# M715X.net
KiCad netlist of a schematic drawn in EAGLE
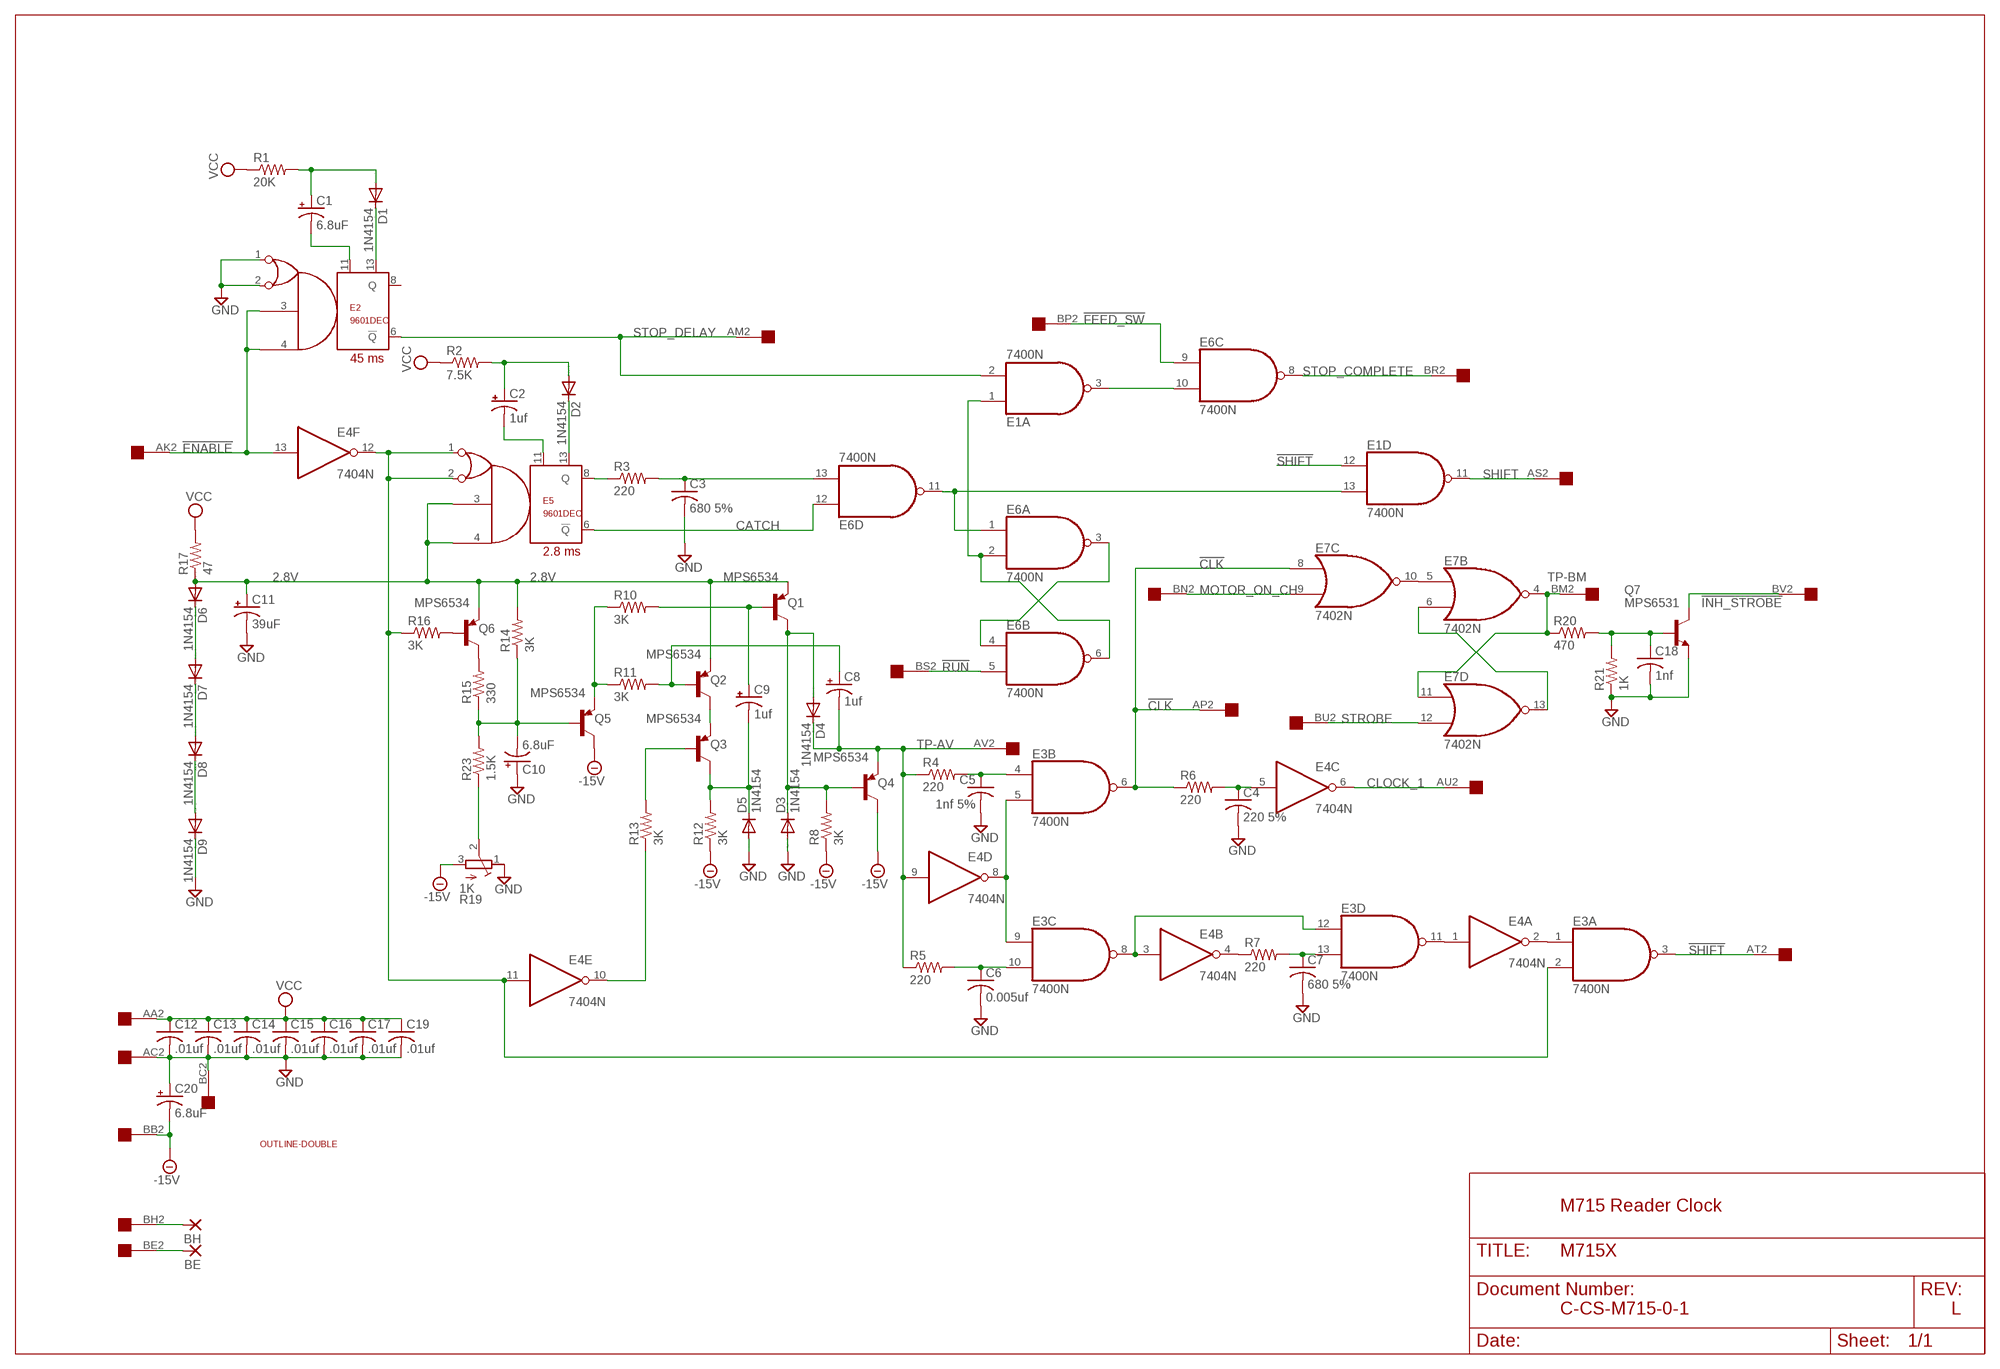
[diagram p0: schematic, sheet 1]

(export (version "E")
  (design (tool "Eeschema 10.0.6"))
  (components
    (comp (ref "BE")
      (value "1,6/0,8")
      (footprint "eagle-import:1,6_0,8")
      (libsource (lib "eagle-import") (part "1,6/0,8"))
    )
    (comp (ref "BH")
      (value "1,6/0,8")
      (footprint "eagle-import:1,6_0,8")
      (libsource (lib "eagle-import") (part "1,6/0,8"))
    )
    (comp (ref "C1")
      (value "6.8uF")
      (footprint "eagle-import:E12-8")
      (libsource (lib "eagle-import") (part "CPOL-USE20-8AXIAL"))
    )
    (comp (ref "C2")
      (value "1uf")
      (footprint "eagle-import:E15-5")
      (libsource (lib "eagle-import") (part "CPOL-USE15-5AXIAL"))
    )
    (comp (ref "C3")
      (value "680 5%")
      (footprint "eagle-import:C050-025X075")
      (libsource (lib "eagle-import") (part "C-US050-025X075"))
    )
    (comp (ref "C4")
      (value "220 5%")
      (footprint "eagle-import:C050-025X075")
      (libsource (lib "eagle-import") (part "C-US050-025X075"))
    )
    (comp (ref "C5")
      (value "1nf 5%")
      (footprint "eagle-import:C050-025X075")
      (libsource (lib "eagle-import") (part "C-US050-025X075"))
    )
    (comp (ref "C6")
      (value "0.005uf")
      (footprint "eagle-import:C050-025X075")
      (libsource (lib "eagle-import") (part "C-US050-025X075"))
    )
    (comp (ref "C7")
      (value "680 5%")
      (footprint "eagle-import:C050-025X075")
      (libsource (lib "eagle-import") (part "C-US050-025X075"))
    )
    (comp (ref "C8")
      (value "1uf")
      (footprint "eagle-import:E15-5")
      (libsource (lib "eagle-import") (part "CPOL-USE15-5AXIAL"))
    )
    (comp (ref "C9")
      (value "1uf")
      (footprint "eagle-import:E15-5")
      (libsource (lib "eagle-import") (part "CPOL-USE15-5AXIAL"))
    )
    (comp (ref "C10")
      (value "6.8uF")
      (footprint "eagle-import:E12-8")
      (libsource (lib "eagle-import") (part "CPOL-USE20-8AXIAL"))
    )
    (comp (ref "C11")
      (value "39uF")
      (footprint "eagle-import:E12-8")
      (libsource (lib "eagle-import") (part "CPOL-USE20-8AXIAL"))
    )
    (comp (ref "C12")
      (value ".01uf")
      (footprint "eagle-import:C050-025X075")
      (libsource (lib "eagle-import") (part "C-US050-025X075"))
    )
    (comp (ref "C13")
      (value ".01uf")
      (footprint "eagle-import:C050-025X075")
      (libsource (lib "eagle-import") (part "C-US050-025X075"))
    )
    (comp (ref "C14")
      (value ".01uf")
      (footprint "eagle-import:C050-025X075")
      (libsource (lib "eagle-import") (part "C-US050-025X075"))
    )
    (comp (ref "C15")
      (value ".01uf")
      (footprint "eagle-import:C050-025X075")
      (libsource (lib "eagle-import") (part "C-US050-025X075"))
    )
    (comp (ref "C16")
      (value ".01uf")
      (footprint "eagle-import:C050-025X075")
      (libsource (lib "eagle-import") (part "C-US050-025X075"))
    )
    (comp (ref "C17")
      (value ".01uf")
      (footprint "eagle-import:C050-025X075")
      (libsource (lib "eagle-import") (part "C-US050-025X075"))
    )
    (comp (ref "C18")
      (value "1nf")
      (footprint "eagle-import:C050-025X075")
      (libsource (lib "eagle-import") (part "C-US050-025X075"))
    )
    (comp (ref "C19")
      (value ".01uf")
      (footprint "eagle-import:C050-025X075")
      (libsource (lib "eagle-import") (part "C-US050-025X075"))
    )
    (comp (ref "C20")
      (value "6.8uF")
      (footprint "eagle-import:E12-8")
      (libsource (lib "eagle-import") (part "CPOL-USE20-8AXIAL"))
    )
    (comp (ref "D1")
      (value "1N4154")
      (footprint "eagle-import:DO35-10")
      (libsource (lib "eagle-import") (part "1N4148DO35-10"))
    )
    (comp (ref "D2")
      (value "1N4154")
      (footprint "eagle-import:DO35-10")
      (libsource (lib "eagle-import") (part "1N4148DO35-10"))
    )
    (comp (ref "D3")
      (value "1N4154")
      (footprint "eagle-import:DO35-10")
      (libsource (lib "eagle-import") (part "1N4148DO35-10"))
    )
    (comp (ref "D4")
      (value "1N4154")
      (footprint "eagle-import:DO35-10")
      (libsource (lib "eagle-import") (part "1N4148DO35-10"))
    )
    (comp (ref "D5")
      (value "1N4154")
      (footprint "eagle-import:DO35-10")
      (libsource (lib "eagle-import") (part "1N4148DO35-10"))
    )
    (comp (ref "D6")
      (value "1N4154")
      (footprint "eagle-import:DO35-10")
      (libsource (lib "eagle-import") (part "1N4148DO35-10"))
    )
    (comp (ref "D7")
      (value "1N4154")
      (footprint "eagle-import:DO35-10")
      (libsource (lib "eagle-import") (part "1N4148DO35-10"))
    )
    (comp (ref "D8")
      (value "1N4154")
      (footprint "eagle-import:DO35-10")
      (libsource (lib "eagle-import") (part "1N4148DO35-10"))
    )
    (comp (ref "D9")
      (value "1N4154")
      (footprint "eagle-import:DO35-10")
      (libsource (lib "eagle-import") (part "1N4148DO35-10"))
    )
    (comp (ref "E1")
      (value "7400N")
      (footprint "eagle-import:DIL14")
      (libsource (lib "eagle-import") (part "7400N"))
    )
    (comp (ref "E2")
      (value "9601DEC")
      (footprint "eagle-import:DIL14")
      (libsource (lib "eagle-import") (part "9601"))
    )
    (comp (ref "E3")
      (value "7400N")
      (footprint "eagle-import:DIL14")
      (libsource (lib "eagle-import") (part "7400N"))
    )
    (comp (ref "E4")
      (value "7404N")
      (footprint "eagle-import:DIL14")
      (libsource (lib "eagle-import") (part "7404N"))
    )
    (comp (ref "E5")
      (value "9601DEC")
      (footprint "eagle-import:DIL14")
      (libsource (lib "eagle-import") (part "9601"))
    )
    (comp (ref "E6")
      (value "7400N")
      (footprint "eagle-import:DIL14")
      (libsource (lib "eagle-import") (part "7400N"))
    )
    (comp (ref "E7")
      (value "7402N")
      (footprint "eagle-import:DIL14")
      (libsource (lib "eagle-import") (part "7402N"))
    )
    (comp (ref "Q1")
      (value "MPS6534")
      (footprint "eagle-import:TO5")
      (libsource (lib "eagle-import") (part "-PNP-TO5"))
    )
    (comp (ref "Q2")
      (value "MPS6534")
      (footprint "eagle-import:TO5")
      (libsource (lib "eagle-import") (part "-PNP-TO5"))
    )
    (comp (ref "Q3")
      (value "MPS6534")
      (footprint "eagle-import:TO5")
      (libsource (lib "eagle-import") (part "-PNP-TO5"))
    )
    (comp (ref "Q4")
      (value "MPS6534")
      (footprint "eagle-import:TO5")
      (libsource (lib "eagle-import") (part "-PNP-TO5"))
    )
    (comp (ref "Q5")
      (value "MPS6534")
      (footprint "eagle-import:TO5")
      (libsource (lib "eagle-import") (part "-PNP-TO5"))
    )
    (comp (ref "Q6")
      (value "MPS6534")
      (footprint "eagle-import:TO5")
      (libsource (lib "eagle-import") (part "-PNP-TO5"))
    )
    (comp (ref "Q7")
      (value "MPS6531")
      (footprint "eagle-import:TO5")
      (libsource (lib "eagle-import") (part "-NPN-TO5"))
    )
    (comp (ref "R1")
      (value "20K")
      (footprint "eagle-import:0207_10")
      (libsource (lib "eagle-import") (part "R-US_0207/10"))
    )
    (comp (ref "R2")
      (value "7.5K")
      (footprint "eagle-import:0207_10")
      (libsource (lib "eagle-import") (part "R-US_0207/10"))
    )
    (comp (ref "R3")
      (value "220")
      (footprint "eagle-import:0207_10")
      (libsource (lib "eagle-import") (part "R-US_0207/10"))
    )
    (comp (ref "R4")
      (value "220")
      (footprint "eagle-import:0207_10")
      (libsource (lib "eagle-import") (part "R-US_0207/10"))
    )
    (comp (ref "R5")
      (value "220")
      (footprint "eagle-import:0207_10")
      (libsource (lib "eagle-import") (part "R-US_0207/10"))
    )
    (comp (ref "R6")
      (value "220")
      (footprint "eagle-import:0207_10")
      (libsource (lib "eagle-import") (part "R-US_0207/10"))
    )
    (comp (ref "R7")
      (value "220")
      (footprint "eagle-import:0207_10")
      (libsource (lib "eagle-import") (part "R-US_0207/10"))
    )
    (comp (ref "R8")
      (value "3K")
      (footprint "eagle-import:0207_10")
      (libsource (lib "eagle-import") (part "R-US_0207/10"))
    )
    (comp (ref "R10")
      (value "3K")
      (footprint "eagle-import:0207_10")
      (libsource (lib "eagle-import") (part "R-US_0207/10"))
    )
    (comp (ref "R11")
      (value "3K")
      (footprint "eagle-import:0207_10")
      (libsource (lib "eagle-import") (part "R-US_0207/10"))
    )
    (comp (ref "R12")
      (value "3K")
      (footprint "eagle-import:0207_10")
      (libsource (lib "eagle-import") (part "R-US_0207/10"))
    )
    (comp (ref "R13")
      (value "3K")
      (footprint "eagle-import:0207_10")
      (libsource (lib "eagle-import") (part "R-US_0207/10"))
    )
    (comp (ref "R14")
      (value "3K")
      (footprint "eagle-import:0207_10")
      (libsource (lib "eagle-import") (part "R-US_0207/10"))
    )
    (comp (ref "R15")
      (value "330")
      (footprint "eagle-import:0207_10")
      (libsource (lib "eagle-import") (part "R-US_0207/10"))
    )
    (comp (ref "R16")
      (value "3K")
      (footprint "eagle-import:0207_10")
      (libsource (lib "eagle-import") (part "R-US_0207/10"))
    )
    (comp (ref "R17")
      (value "47")
      (footprint "eagle-import:0207_10")
      (libsource (lib "eagle-import") (part "R-US_0207/10"))
    )
    (comp (ref "R19")
      (value "1K")
      (footprint "eagle-import:3006Y")
      (libsource (lib "eagle-import") (part "275P"))
    )
    (comp (ref "R20")
      (value "470")
      (footprint "eagle-import:0207_10")
      (libsource (lib "eagle-import") (part "R-US_0207/10"))
    )
    (comp (ref "R21")
      (value "1K")
      (footprint "eagle-import:0207_10")
      (libsource (lib "eagle-import") (part "R-US_0207/10"))
    )
    (comp (ref "R23")
      (value "1.5K")
      (footprint "eagle-import:0207_10")
      (libsource (lib "eagle-import") (part "R-US_0207/10"))
    )
    (comp (ref "U$1")
      (value "DOUBLE")
      (footprint "eagle-import:EDGE-CON4")
      (libsource (lib "eagle-import") (part "DOUBLE"))
    )
    (comp (ref "U$2")
      (value "OUTLINE-DOUBLE")
      (footprint "eagle-import:DOUBLE")
      (libsource (lib "eagle-import") (part "OUTLINE-DOUBLE"))
    )
  )
  (nets
    (net (code "1") (name "-15V") (class "Default")
      (node (ref "C20") (pin "-") (pinfunction "-_-") (pintype "passive"))
      (node (ref "Q4") (pin "3") (pinfunction "C_3") (pintype "passive"))
      (node (ref "Q5") (pin "3") (pinfunction "C_3") (pintype "passive"))
      (node (ref "R12") (pin "1") (pinfunction "1_1") (pintype "passive"))
      (node (ref "R19") (pin "3") (pinfunction "E_3") (pintype "passive"))
      (node (ref "R8") (pin "1") (pinfunction "1_1") (pintype "passive"))
      (node (ref "U$1") (pin "BB2") (pinfunction "1_BB2") (pintype "bidirectional"))
    )
    (net (code "2") (name "/2.8V") (class "Default")
      (node (ref "C11") (pin "+") (pinfunction "+_+") (pintype "passive"))
      (node (ref "D6") (pin "A") (pinfunction "A_A") (pintype "passive"))
      (node (ref "E5") (pin "3") (pinfunction "P$3_3") (pintype "input"))
      (node (ref "E5") (pin "4") (pinfunction "P$4_4") (pintype "input"))
      (node (ref "Q1") (pin "1") (pinfunction "E_1") (pintype "passive"))
      (node (ref "Q2") (pin "1") (pinfunction "E_1") (pintype "passive"))
      (node (ref "Q6") (pin "1") (pinfunction "E_1") (pintype "passive"))
      (node (ref "R14") (pin "2") (pinfunction "2_2") (pintype "passive"))
      (node (ref "R17") (pin "1") (pinfunction "1_1") (pintype "passive"))
    )
    (net (code "3") (name "/CATCH") (class "Default")
      (node (ref "E5") (pin "6") (pinfunction "~{Q}_6") (pintype "output"))
      (node (ref "E6") (pin "12") (pinfunction "I0_12") (pintype "input"))
    )
    (net (code "4") (name "/CLOCK_1") (class "Default")
      (node (ref "E4") (pin "6") (pinfunction "O_6") (pintype "output"))
      (node (ref "U$1") (pin "AU2") (pinfunction "1_AU2") (pintype "bidirectional"))
    )
    (net (code "5") (name "/MOTOR_ON_CH") (class "Default")
      (node (ref "E7") (pin "9") (pinfunction "I1_9") (pintype "input"))
      (node (ref "U$1") (pin "BN2") (pinfunction "1_BN2") (pintype "bidirectional"))
    )
    (net (code "6") (name "/SHIFT") (class "Default")
      (node (ref "E1") (pin "11") (pinfunction "O_11") (pintype "output"))
      (node (ref "U$1") (pin "AS2") (pinfunction "1_AS2") (pintype "bidirectional"))
    )
    (net (code "7") (name "/STOP_COMPLETE") (class "Default")
      (node (ref "E6") (pin "8") (pinfunction "O_8") (pintype "output"))
      (node (ref "U$1") (pin "BR2") (pinfunction "1_BR2") (pintype "bidirectional"))
    )
    (net (code "8") (name "/STOP_DELAY") (class "Default")
      (node (ref "E1") (pin "2") (pinfunction "I1_2") (pintype "input"))
      (node (ref "E2") (pin "6") (pinfunction "~{Q}_6") (pintype "output"))
      (node (ref "U$1") (pin "AM2") (pinfunction "1_AM2") (pintype "bidirectional"))
    )
    (net (code "9") (name "/STROBE") (class "Default")
      (node (ref "E7") (pin "12") (pinfunction "I1_12") (pintype "input"))
      (node (ref "U$1") (pin "BU2") (pinfunction "1_BU2") (pintype "bidirectional"))
    )
    (net (code "10") (name "/TP-AV") (class "Default")
      (node (ref "C8") (pin "-") (pinfunction "-_-") (pintype "passive"))
      (node (ref "D4") (pin "C") (pinfunction "C_C") (pintype "passive"))
      (node (ref "E4") (pin "9") (pinfunction "I_9") (pintype "input"))
      (node (ref "Q4") (pin "1") (pinfunction "E_1") (pintype "passive"))
      (node (ref "R4") (pin "1") (pinfunction "1_1") (pintype "passive"))
      (node (ref "R5") (pin "1") (pinfunction "1_1") (pintype "passive"))
      (node (ref "U$1") (pin "AV2") (pinfunction "1_AV2") (pintype "bidirectional"))
    )
    (net (code "11") (name "/TP-BM") (class "Default")
      (node (ref "E7") (pin "11") (pinfunction "I0_11") (pintype "input"))
      (node (ref "E7") (pin "4") (pinfunction "O_4") (pintype "output"))
      (node (ref "R20") (pin "1") (pinfunction "1_1") (pintype "passive"))
      (node (ref "U$1") (pin "BM2") (pinfunction "1_BM2") (pintype "bidirectional"))
    )
    (net (code "12") (name "/~{CLK}") (class "Default")
      (node (ref "E3") (pin "6") (pinfunction "O_6") (pintype "output"))
      (node (ref "E7") (pin "8") (pinfunction "I0_8") (pintype "input"))
      (node (ref "R6") (pin "1") (pinfunction "1_1") (pintype "passive"))
      (node (ref "U$1") (pin "AP2") (pinfunction "1_AP2") (pintype "bidirectional"))
    )
    (net (code "13") (name "/~{ENABLE}") (class "Default")
      (node (ref "E2") (pin "3") (pinfunction "P$3_3") (pintype "input"))
      (node (ref "E2") (pin "4") (pinfunction "P$4_4") (pintype "input"))
      (node (ref "E4") (pin "13") (pinfunction "I_13") (pintype "input"))
      (node (ref "U$1") (pin "AK2") (pinfunction "1_AK2") (pintype "bidirectional"))
    )
    (net (code "14") (name "/~{FEED_SW}") (class "Default")
      (node (ref "E6") (pin "9") (pinfunction "I0_9") (pintype "input"))
      (node (ref "U$1") (pin "BP2") (pinfunction "1_BP2") (pintype "bidirectional"))
    )
    (net (code "15") (name "/~{INH_STROBE}") (class "Default")
      (node (ref "Q7") (pin "3") (pinfunction "C_3") (pintype "passive"))
      (node (ref "U$1") (pin "BV2") (pinfunction "1_BV2") (pintype "bidirectional"))
    )
    (net (code "16") (name "/~{RUN}") (class "Default")
      (node (ref "E6") (pin "5") (pinfunction "I1_5") (pintype "input"))
      (node (ref "U$1") (pin "BS2") (pinfunction "1_BS2") (pintype "bidirectional"))
    )
    (net (code "17") (name "/~{SHIFT}") (class "Default")
      (node (ref "E1") (pin "12") (pinfunction "I0_12") (pintype "input"))
      (node (ref "E3") (pin "3") (pinfunction "O_3") (pintype "output"))
      (node (ref "U$1") (pin "AT2") (pinfunction "1_AT2") (pintype "bidirectional"))
    )
    (net (code "18") (name "GND") (class "Default")
      (node (ref "C10") (pin "+") (pinfunction "+_+") (pintype "passive"))
      (node (ref "C11") (pin "-") (pinfunction "-_-") (pintype "passive"))
      (node (ref "C12") (pin "2") (pinfunction "2_2") (pintype "passive"))
      (node (ref "C13") (pin "2") (pinfunction "2_2") (pintype "passive"))
      (node (ref "C14") (pin "2") (pinfunction "2_2") (pintype "passive"))
      (node (ref "C15") (pin "2") (pinfunction "2_2") (pintype "passive"))
      (node (ref "C16") (pin "2") (pinfunction "2_2") (pintype "passive"))
      (node (ref "C17") (pin "2") (pinfunction "2_2") (pintype "passive"))
      (node (ref "C18") (pin "2") (pinfunction "2_2") (pintype "passive"))
      (node (ref "C19") (pin "2") (pinfunction "2_2") (pintype "passive"))
      (node (ref "C20") (pin "+") (pinfunction "+_+") (pintype "passive"))
      (node (ref "C3") (pin "2") (pinfunction "2_2") (pintype "passive"))
      (node (ref "C4") (pin "2") (pinfunction "2_2") (pintype "passive"))
      (node (ref "C5") (pin "2") (pinfunction "2_2") (pintype "passive"))
      (node (ref "C6") (pin "2") (pinfunction "2_2") (pintype "passive"))
      (node (ref "C7") (pin "2") (pinfunction "2_2") (pintype "passive"))
      (node (ref "D3") (pin "A") (pinfunction "A_A") (pintype "passive"))
      (node (ref "D5") (pin "A") (pinfunction "A_A") (pintype "passive"))
      (node (ref "D9") (pin "C") (pinfunction "C_C") (pintype "passive"))
      (node (ref "E2") (pin "1") (pinfunction "P$1_1") (pintype "input"))
      (node (ref "E2") (pin "2") (pinfunction "P$2_2") (pintype "input"))
      (node (ref "Q7") (pin "1") (pinfunction "E_1") (pintype "passive"))
      (node (ref "R19") (pin "1") (pinfunction "A_1") (pintype "passive"))
      (node (ref "R21") (pin "1") (pinfunction "1_1") (pintype "passive"))
      (node (ref "U$1") (pin "AC2") (pinfunction "1_AC2") (pintype "bidirectional"))
      (node (ref "U$1") (pin "BC2") (pinfunction "1_BC2") (pintype "bidirectional"))
    )
    (net (code "19") (name "Net-(BE-P)") (class "Default")
      (node (ref "BE") (pin "1") (pinfunction "P_1") (pintype "passive"))
      (node (ref "U$1") (pin "BE2") (pinfunction "1_BE2") (pintype "bidirectional"))
    )
    (net (code "20") (name "Net-(BH-P)") (class "Default")
      (node (ref "BH") (pin "1") (pinfunction "P_1") (pintype "passive"))
      (node (ref "U$1") (pin "BH2") (pinfunction "1_BH2") (pintype "bidirectional"))
    )
    (net (code "21") (name "Net-(C1-Pad+)") (class "Default")
      (node (ref "C1") (pin "+") (pinfunction "+_+") (pintype "passive"))
      (node (ref "D1") (pin "A") (pinfunction "A_A") (pintype "passive"))
      (node (ref "R1") (pin "2") (pinfunction "2_2") (pintype "passive"))
    )
    (net (code "22") (name "Net-(C2-Pad+)") (class "Default")
      (node (ref "C2") (pin "+") (pinfunction "+_+") (pintype "passive"))
      (node (ref "D2") (pin "A") (pinfunction "A_A") (pintype "passive"))
      (node (ref "R2") (pin "2") (pinfunction "2_2") (pintype "passive"))
    )
    (net (code "23") (name "Net-(D6-PadC)") (class "Default")
      (node (ref "D6") (pin "C") (pinfunction "C_C") (pintype "passive"))
      (node (ref "D7") (pin "A") (pinfunction "A_A") (pintype "passive"))
    )
    (net (code "24") (name "Net-(D7-PadC)") (class "Default")
      (node (ref "D7") (pin "C") (pinfunction "C_C") (pintype "passive"))
      (node (ref "D8") (pin "A") (pinfunction "A_A") (pintype "passive"))
    )
    (net (code "25") (name "Net-(D8-PadC)") (class "Default")
      (node (ref "D8") (pin "C") (pinfunction "C_C") (pintype "passive"))
      (node (ref "D9") (pin "A") (pinfunction "A_A") (pintype "passive"))
    )
    (net (code "26") (name "Net-(E1A-I0)") (class "Default")
      (node (ref "E1") (pin "1") (pinfunction "I0_1") (pintype "input"))
      (node (ref "E6") (pin "2") (pinfunction "I1_2") (pintype "input"))
      (node (ref "E6") (pin "6") (pinfunction "O_6") (pintype "output"))
    )
    (net (code "27") (name "Net-(E1A-O)") (class "Default")
      (node (ref "E1") (pin "3") (pinfunction "O_3") (pintype "output"))
      (node (ref "E6") (pin "10") (pinfunction "I1_10") (pintype "input"))
    )
    (net (code "28") (name "Net-(E1D-I1)") (class "Default")
      (node (ref "E1") (pin "13") (pinfunction "I1_13") (pintype "input"))
      (node (ref "E6") (pin "1") (pinfunction "I0_1") (pintype "input"))
      (node (ref "E6") (pin "11") (pinfunction "O_11") (pintype "output"))
    )
    (net (code "29") (name "Net-(E2A-P$5)") (class "Default")
      (node (ref "C1") (pin "-") (pinfunction "-_-") (pintype "passive"))
      (node (ref "E2") (pin "11") (pinfunction "P$5_11") (pintype "bidirectional"))
    )
    (net (code "30") (name "Net-(E2A-P$6)") (class "Default")
      (node (ref "D1") (pin "C") (pinfunction "C_C") (pintype "passive"))
      (node (ref "E2") (pin "13") (pinfunction "P$6_13") (pintype "bidirectional"))
    )
    (net (code "31") (name "Net-(E3A-I0)") (class "Default")
      (node (ref "E3") (pin "1") (pinfunction "I0_1") (pintype "input"))
      (node (ref "E4") (pin "2") (pinfunction "O_2") (pintype "output"))
    )
    (net (code "32") (name "Net-(E3A-I1)") (class "Default")
      (node (ref "E3") (pin "2") (pinfunction "I1_2") (pintype "input"))
      (node (ref "E4") (pin "11") (pinfunction "I_11") (pintype "input"))
      (node (ref "E4") (pin "12") (pinfunction "O_12") (pintype "output"))
      (node (ref "E5") (pin "1") (pinfunction "P$1_1") (pintype "input"))
      (node (ref "E5") (pin "2") (pinfunction "P$2_2") (pintype "input"))
      (node (ref "R16") (pin "1") (pinfunction "1_1") (pintype "passive"))
    )
    (net (code "33") (name "Net-(E3B-I0)") (class "Default")
      (node (ref "C5") (pin "1") (pinfunction "1_1") (pintype "passive"))
      (node (ref "E3") (pin "4") (pinfunction "I0_4") (pintype "input"))
      (node (ref "R4") (pin "2") (pinfunction "2_2") (pintype "passive"))
    )
    (net (code "34") (name "Net-(E3B-I1)") (class "Default")
      (node (ref "E3") (pin "5") (pinfunction "I1_5") (pintype "input"))
      (node (ref "E3") (pin "9") (pinfunction "I0_9") (pintype "input"))
      (node (ref "E4") (pin "8") (pinfunction "O_8") (pintype "output"))
    )
    (net (code "35") (name "Net-(E3C-I1)") (class "Default")
      (node (ref "C6") (pin "1") (pinfunction "1_1") (pintype "passive"))
      (node (ref "E3") (pin "10") (pinfunction "I1_10") (pintype "input"))
      (node (ref "R5") (pin "2") (pinfunction "2_2") (pintype "passive"))
    )
    (net (code "36") (name "Net-(E3C-O)") (class "Default")
      (node (ref "E3") (pin "12") (pinfunction "I0_12") (pintype "input"))
      (node (ref "E3") (pin "8") (pinfunction "O_8") (pintype "output"))
      (node (ref "E4") (pin "3") (pinfunction "I_3") (pintype "input"))
    )
    (net (code "37") (name "Net-(E3D-I1)") (class "Default")
      (node (ref "C7") (pin "1") (pinfunction "1_1") (pintype "passive"))
      (node (ref "E3") (pin "13") (pinfunction "I1_13") (pintype "input"))
      (node (ref "R7") (pin "2") (pinfunction "2_2") (pintype "passive"))
    )
    (net (code "38") (name "Net-(E3D-O)") (class "Default")
      (node (ref "E3") (pin "11") (pinfunction "O_11") (pintype "output"))
      (node (ref "E4") (pin "1") (pinfunction "I_1") (pintype "input"))
    )
    (net (code "39") (name "Net-(E4B-O)") (class "Default")
      (node (ref "E4") (pin "4") (pinfunction "O_4") (pintype "output"))
      (node (ref "R7") (pin "1") (pinfunction "1_1") (pintype "passive"))
    )
    (net (code "40") (name "Net-(E4C-I)") (class "Default")
      (node (ref "C4") (pin "1") (pinfunction "1_1") (pintype "passive"))
      (node (ref "E4") (pin "5") (pinfunction "I_5") (pintype "input"))
      (node (ref "R6") (pin "2") (pinfunction "2_2") (pintype "passive"))
    )
    (net (code "41") (name "Net-(E4E-O)") (class "Default")
      (node (ref "E4") (pin "10") (pinfunction "O_10") (pintype "output"))
      (node (ref "R13") (pin "1") (pinfunction "1_1") (pintype "passive"))
    )
    (net (code "42") (name "Net-(E5A-P$5)") (class "Default")
      (node (ref "C2") (pin "-") (pinfunction "-_-") (pintype "passive"))
      (node (ref "E5") (pin "11") (pinfunction "P$5_11") (pintype "bidirectional"))
    )
    (net (code "43") (name "Net-(E5A-P$6)") (class "Default")
      (node (ref "D2") (pin "C") (pinfunction "C_C") (pintype "passive"))
      (node (ref "E5") (pin "13") (pinfunction "P$6_13") (pintype "bidirectional"))
    )
    (net (code "44") (name "Net-(E5A-Q)") (class "Default")
      (node (ref "E5") (pin "8") (pinfunction "Q_8") (pintype "output"))
      (node (ref "R3") (pin "1") (pinfunction "1_1") (pintype "passive"))
    )
    (net (code "45") (name "Net-(E6A-O)") (class "Default")
      (node (ref "E6") (pin "3") (pinfunction "O_3") (pintype "output"))
      (node (ref "E6") (pin "4") (pinfunction "I0_4") (pintype "input"))
    )
    (net (code "46") (name "Net-(E6D-I1)") (class "Default")
      (node (ref "C3") (pin "1") (pinfunction "1_1") (pintype "passive"))
      (node (ref "E6") (pin "13") (pinfunction "I1_13") (pintype "input"))
      (node (ref "R3") (pin "2") (pinfunction "2_2") (pintype "passive"))
    )
    (net (code "47") (name "Net-(E7B-I0)") (class "Default")
      (node (ref "E7") (pin "10") (pinfunction "O_10") (pintype "output"))
      (node (ref "E7") (pin "5") (pinfunction "I0_5") (pintype "input"))
    )
    (net (code "48") (name "Net-(E7B-I1)") (class "Default")
      (node (ref "E7") (pin "13") (pinfunction "O_13") (pintype "output"))
      (node (ref "E7") (pin "6") (pinfunction "I1_6") (pintype "input"))
    )
    (net (code "49") (name "Net-(Q1-B)") (class "Default")
      (node (ref "C9") (pin "+") (pinfunction "+_+") (pintype "passive"))
      (node (ref "Q1") (pin "2") (pinfunction "B_2") (pintype "passive"))
      (node (ref "R10") (pin "2") (pinfunction "2_2") (pintype "passive"))
    )
    (net (code "50") (name "Net-(Q1-C)") (class "Default")
      (node (ref "D3") (pin "C") (pinfunction "C_C") (pintype "passive"))
      (node (ref "D4") (pin "A") (pinfunction "A_A") (pintype "passive"))
      (node (ref "Q1") (pin "3") (pinfunction "C_3") (pintype "passive"))
      (node (ref "Q4") (pin "2") (pinfunction "B_2") (pintype "passive"))
      (node (ref "R8") (pin "2") (pinfunction "2_2") (pintype "passive"))
    )
    (net (code "51") (name "Net-(Q2-B)") (class "Default")
      (node (ref "C8") (pin "+") (pinfunction "+_+") (pintype "passive"))
      (node (ref "Q2") (pin "2") (pinfunction "B_2") (pintype "passive"))
      (node (ref "R11") (pin "2") (pinfunction "2_2") (pintype "passive"))
    )
    (net (code "52") (name "Net-(Q2-C)") (class "Default")
      (node (ref "Q2") (pin "3") (pinfunction "C_3") (pintype "passive"))
      (node (ref "Q3") (pin "1") (pinfunction "E_1") (pintype "passive"))
    )
    (net (code "53") (name "Net-(Q3-B)") (class "Default")
      (node (ref "Q3") (pin "2") (pinfunction "B_2") (pintype "passive"))
      (node (ref "R13") (pin "2") (pinfunction "2_2") (pintype "passive"))
    )
    (net (code "54") (name "Net-(Q3-C)") (class "Default")
      (node (ref "C9") (pin "-") (pinfunction "-_-") (pintype "passive"))
      (node (ref "D5") (pin "C") (pinfunction "C_C") (pintype "passive"))
      (node (ref "Q3") (pin "3") (pinfunction "C_3") (pintype "passive"))
      (node (ref "R12") (pin "2") (pinfunction "2_2") (pintype "passive"))
    )
    (net (code "55") (name "Net-(Q5-B)") (class "Default")
      (node (ref "C10") (pin "-") (pinfunction "-_-") (pintype "passive"))
      (node (ref "Q5") (pin "2") (pinfunction "B_2") (pintype "passive"))
      (node (ref "R14") (pin "1") (pinfunction "1_1") (pintype "passive"))
      (node (ref "R15") (pin "1") (pinfunction "1_1") (pintype "passive"))
      (node (ref "R23") (pin "2") (pinfunction "2_2") (pintype "passive"))
    )
    (net (code "56") (name "Net-(Q5-E)") (class "Default")
      (node (ref "Q5") (pin "1") (pinfunction "E_1") (pintype "passive"))
      (node (ref "R10") (pin "1") (pinfunction "1_1") (pintype "passive"))
      (node (ref "R11") (pin "1") (pinfunction "1_1") (pintype "passive"))
    )
    (net (code "57") (name "Net-(Q6-B)") (class "Default")
      (node (ref "Q6") (pin "2") (pinfunction "B_2") (pintype "passive"))
      (node (ref "R16") (pin "2") (pinfunction "2_2") (pintype "passive"))
    )
    (net (code "58") (name "Net-(Q6-C)") (class "Default")
      (node (ref "Q6") (pin "3") (pinfunction "C_3") (pintype "passive"))
      (node (ref "R15") (pin "2") (pinfunction "2_2") (pintype "passive"))
    )
    (net (code "59") (name "Net-(Q7-B)") (class "Default")
      (node (ref "C18") (pin "1") (pinfunction "1_1") (pintype "passive"))
      (node (ref "Q7") (pin "2") (pinfunction "B_2") (pintype "passive"))
      (node (ref "R20") (pin "2") (pinfunction "2_2") (pintype "passive"))
      (node (ref "R21") (pin "2") (pinfunction "2_2") (pintype "passive"))
    )
    (net (code "60") (name "Net-(R19-S)") (class "Default")
      (node (ref "R19") (pin "2") (pinfunction "S_2") (pintype "passive"))
      (node (ref "R23") (pin "1") (pinfunction "1_1") (pintype "passive"))
    )
    (net (code "61") (name "VCC") (class "Default")
      (node (ref "C12") (pin "1") (pinfunction "1_1") (pintype "passive"))
      (node (ref "C13") (pin "1") (pinfunction "1_1") (pintype "passive"))
      (node (ref "C14") (pin "1") (pinfunction "1_1") (pintype "passive"))
      (node (ref "C15") (pin "1") (pinfunction "1_1") (pintype "passive"))
      (node (ref "C16") (pin "1") (pinfunction "1_1") (pintype "passive"))
      (node (ref "C17") (pin "1") (pinfunction "1_1") (pintype "passive"))
      (node (ref "C19") (pin "1") (pinfunction "1_1") (pintype "passive"))
      (node (ref "R1") (pin "1") (pinfunction "1_1") (pintype "passive"))
      (node (ref "R17") (pin "2") (pinfunction "2_2") (pintype "passive"))
      (node (ref "R2") (pin "1") (pinfunction "1_1") (pintype "passive"))
      (node (ref "U$1") (pin "AA2") (pinfunction "1_AA2") (pintype "bidirectional"))
    )
    (net (code "62") (name "unconnected-(E2A-Q-Pad8)") (class "Default")
      (node (ref "E2") (pin "8") (pinfunction "Q_8") (pintype "output"))
    )
  )
)
